# LDO_AUX.net
KiCad netlist of a schematic drawn in Altium Designer
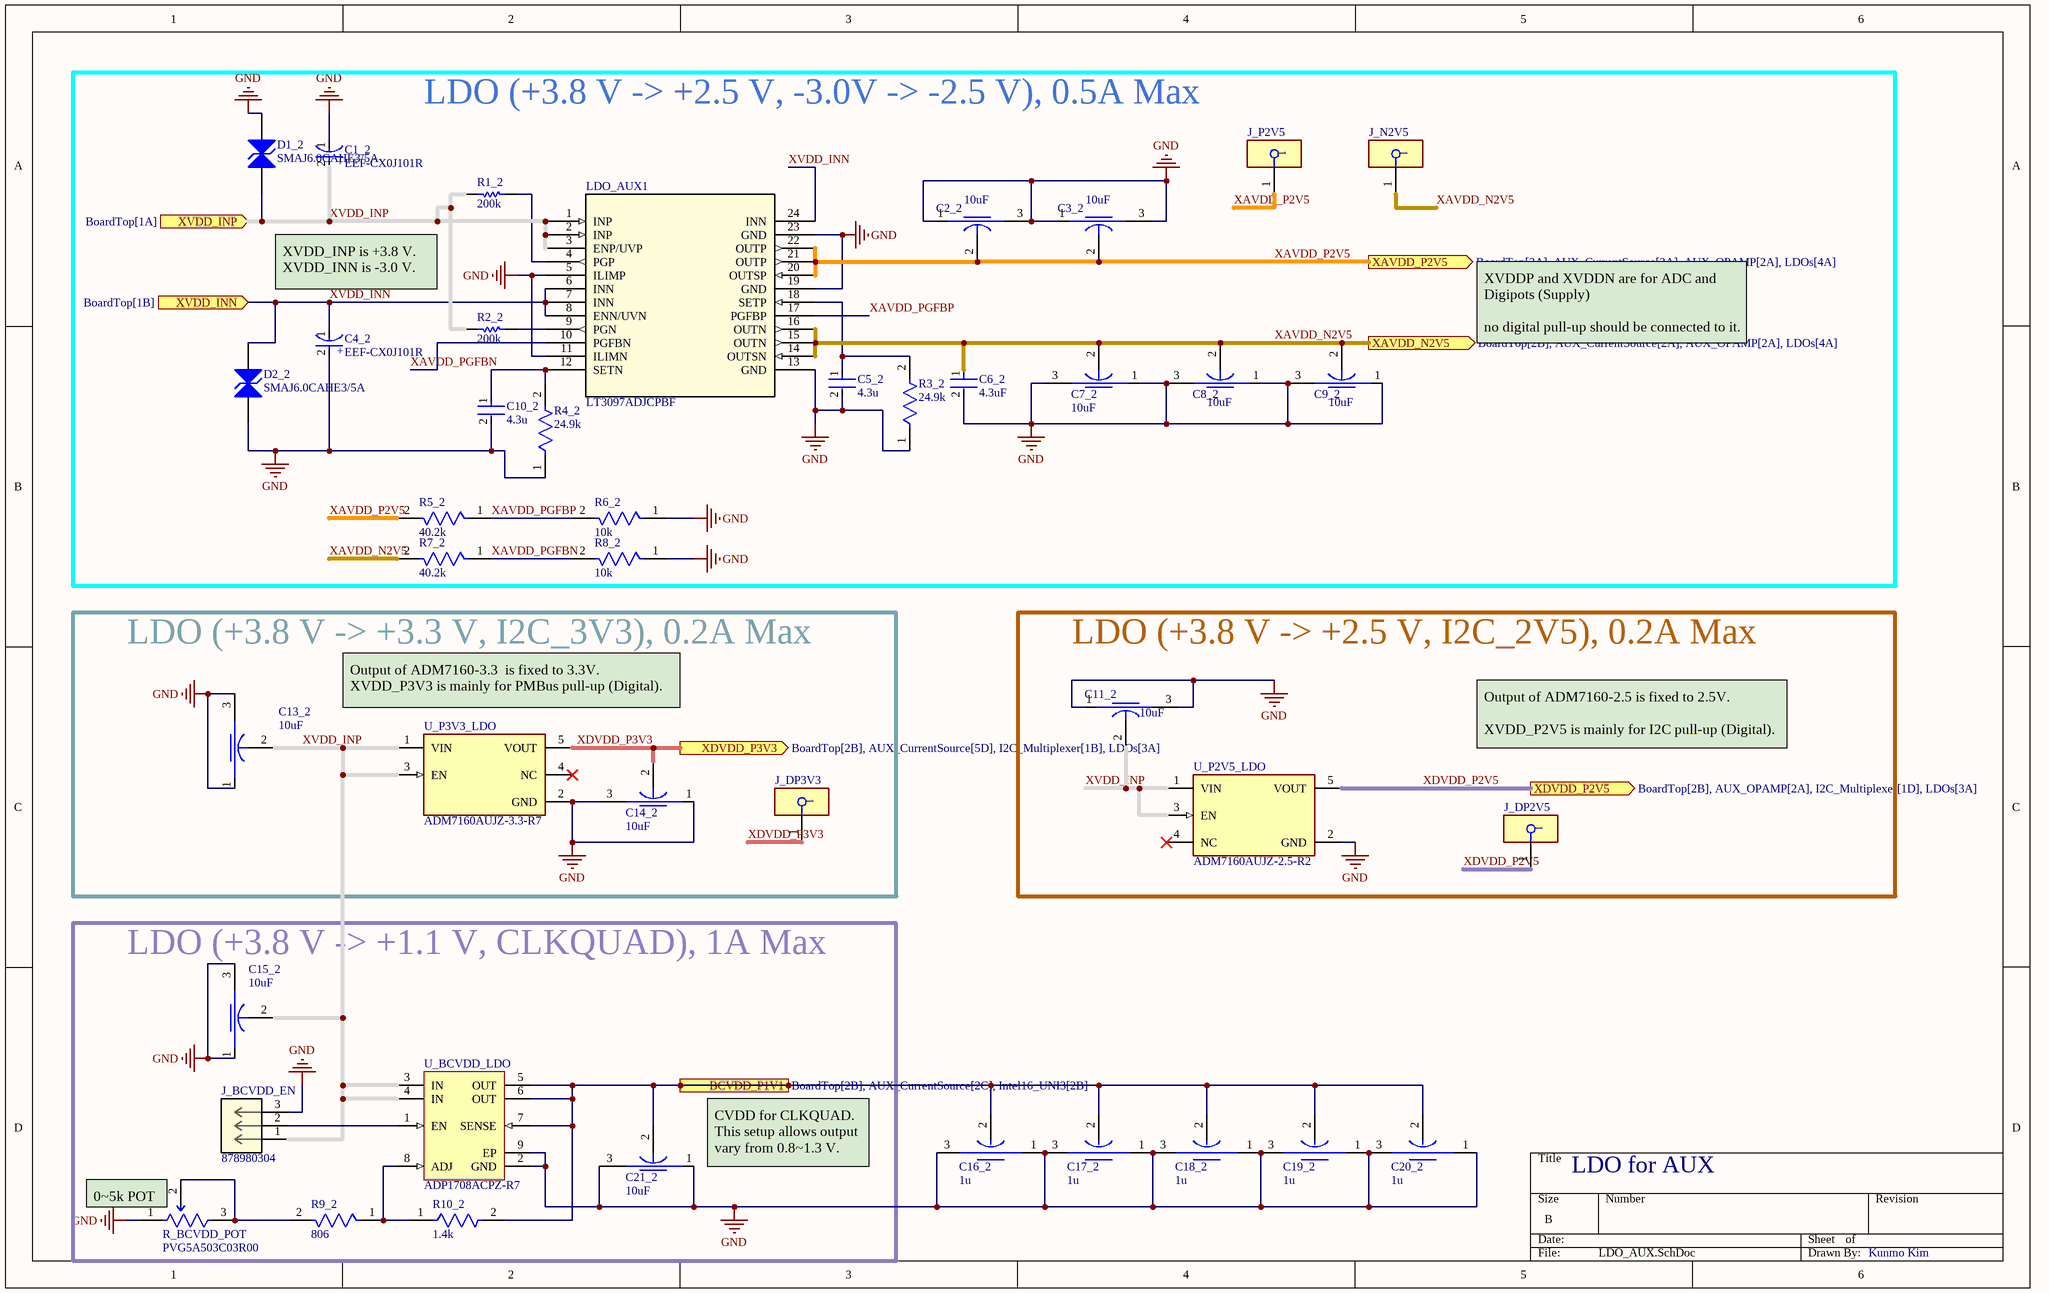
[diagram p0: LDO_AUX.SchDoc]

(export (version "E")
  (design (tool "Eeschema 10.0.6"))
  (components
    (comp (ref "C1_2")
      (value "EEF-CX0J101R")
      (footprint "FP-CX-MFG")
      (description "CAP ALUM POLY 100UF 20% 6.3V SMD")
      (fields (field (name "VOLTAGE") "6.3V") (field (name "TOLERANCE") "20%"))
      (libsource (lib "cap_SP_100uF") (part "CMP-05427-000056-1"))
    )
    (comp (ref "C2_2")
      (value "10uF")
      (footprint "FP-NFM15-0_2-MFG")
      (description "CAP FEEDTHRU")
      (libsource (lib "NFM15PC915") (part "CMP-06053-000058-1"))
    )
    (comp (ref "C3_2")
      (value "10uF")
      (footprint "FP-NFM15-0_2-MFG")
      (description "CAP FEEDTHRU")
      (libsource (lib "NFM15PC915") (part "CMP-06053-000058-1"))
    )
    (comp (ref "C4_2")
      (value "EEF-CX0J101R")
      (footprint "FP-CX-MFG")
      (description "CAP ALUM POLY 100UF 20% 6.3V SMD")
      (fields (field (name "VOLTAGE") "6.3V") (field (name "TOLERANCE") "20%"))
      (libsource (lib "cap_SP_100uF") (part "CMP-05427-000056-1"))
    )
    (comp (ref "C5_2")
      (value "4.3u")
      (footprint "FP-LLL1U4-0_05-IPC_C")
      (description "Cap Ceramic Monolithic 4.3uF 20% 4V X5R 15% 02404 (0610M)")
      (fields (field (name "TOLERANCE") "20%"))
      (libsource (lib "LLL_cap") (part "CMP-06035-061933-1"))
    )
    (comp (ref "C6_2")
      (value "4.3uF")
      (footprint "FP-LLL1U4-0_05-MFG")
      (description "Cap Ceramic Monolithic 4.3uF 20% 4V X5R 15% 02404 (0610M)")
      (fields (field (name "TOLERANCE") "20%"))
      (libsource (lib "LLL_cap") (part "CMP-06035-061933-1"))
    )
    (comp (ref "C7_2")
      (value "10uF")
      (footprint "FP-NFM15-0_2-MFG")
      (description "CAP FEEDTHRU")
      (libsource (lib "NFM15PC915") (part "CMP-06053-000058-1"))
    )
    (comp (ref "C8_2")
      (value "10uF")
      (footprint "FP-NFM15-0_2-MFG")
      (description "CAP FEEDTHRU")
      (libsource (lib "NFM15PC915") (part "CMP-06053-000058-1"))
    )
    (comp (ref "C9_2")
      (value "10uF")
      (footprint "FP-NFM15-0_2-MFG")
      (description "CAP FEEDTHRU")
      (libsource (lib "NFM15PC915") (part "CMP-06053-000058-1"))
    )
    (comp (ref "C10_2")
      (value "4.3u")
      (footprint "FP-LLL1U4-0_05-IPC_C")
      (description "Cap Ceramic Monolithic 4.3uF 20% 4V X5R 15% 02404 (0610M)")
      (fields (field (name "TOLERANCE") "20%"))
      (libsource (lib "LLL_cap") (part "CMP-06035-061933-1"))
    )
    (comp (ref "C11_2")
      (value "10uF")
      (footprint "FP-NFM15-0_2-MFG")
      (description "CAP FEEDTHRU")
      (libsource (lib "NFM15PC915") (part "CMP-06053-000058-1"))
    )
    (comp (ref "C13_2")
      (value "10uF")
      (footprint "FP-NFM15-0_2-MFG")
      (description "CAP FEEDTHRU")
      (libsource (lib "NFM15PC915") (part "CMP-06053-000058-1"))
    )
    (comp (ref "C14_2")
      (value "10uF")
      (footprint "FP-NFM15-0_2-MFG")
      (description "CAP FEEDTHRU")
      (libsource (lib "NFM15PC915") (part "CMP-06053-000058-1"))
    )
    (comp (ref "C15_2")
      (value "10uF")
      (footprint "FP-NFM15-0_2-MFG")
      (description "CAP FEEDTHRU")
      (libsource (lib "NFM15PC915") (part "CMP-06053-000058-1"))
    )
    (comp (ref "C16_2")
      (value "1u")
      (footprint "PCBComponent_1")
      (description "0402(1005M) 4V 1.0UF +/- 20% 3 T")
      (fields (field (name "TOLERANCE") "20%"))
      (libsource (lib "NFM15HC105D0G3D") (part "CMP-06053-000757-1"))
    )
    (comp (ref "C17_2")
      (value "1u")
      (footprint "PCBComponent_1")
      (description "0402(1005M) 4V 1.0UF +/- 20% 3 T")
      (fields (field (name "TOLERANCE") "20%"))
      (libsource (lib "NFM15HC105D0G3D") (part "CMP-06053-000757-1"))
    )
    (comp (ref "C18_2")
      (value "1u")
      (footprint "PCBComponent_1")
      (description "0402(1005M) 4V 1.0UF +/- 20% 3 T")
      (fields (field (name "TOLERANCE") "20%"))
      (libsource (lib "NFM15HC105D0G3D") (part "CMP-06053-000757-1"))
    )
    (comp (ref "C19_2")
      (value "1u")
      (footprint "PCBComponent_1")
      (description "0402(1005M) 4V 1.0UF +/- 20% 3 T")
      (fields (field (name "TOLERANCE") "20%"))
      (libsource (lib "NFM15HC105D0G3D") (part "CMP-06053-000757-1"))
    )
    (comp (ref "C20_2")
      (value "1u")
      (footprint "PCBComponent_1")
      (description "0402(1005M) 4V 1.0UF +/- 20% 3 T")
      (fields (field (name "TOLERANCE") "20%"))
      (libsource (lib "NFM15HC105D0G3D") (part "CMP-06053-000757-1"))
    )
    (comp (ref "C21_2")
      (value "10uF")
      (footprint "FP-NFM15-0_2-MFG")
      (description "CAP FEEDTHRU")
      (libsource (lib "NFM15PC915") (part "CMP-06053-000058-1"))
    )
    (comp (ref "D1_2")
      (value "SMAJ6.0CAHE3/5A")
      (footprint "VISH-DO-214AC-2_L")
      (fields (field (name "MANUFACTURER") "Vishay Semiconductor"))
      (libsource (lib "SMAJ6p0CAHE3") (part "CMP-0548-00108-2"))
    )
    (comp (ref "D2_2")
      (value "SMAJ6.0CAHE3/5A")
      (footprint "VISH-DO-214AC-2_L")
      (fields (field (name "MANUFACTURER") "Vishay Semiconductor"))
      (libsource (lib "SMAJ6p0CAHE3") (part "CMP-0548-00108-2"))
    )
    (comp (ref "J_BCVDD_EN")
      (value "878980304")
      (footprint "CONN03_87898_M-5p84_MOL")
      (description "No Description Available")
      (libsource (lib "878980304") (part "878980304"))
    )
    (comp (ref "J_DP2V5")
      (value "5019")
      (footprint "FP-5019-MFG")
      (libsource (lib "Altium Content Vault") (part "98815daf2f2c152b0c43f5ab9800df6"))
    )
    (comp (ref "J_DP3V3")
      (value "5019")
      (footprint "FP-5019-MFG")
      (libsource (lib "Altium Content Vault") (part "98815daf2f2c152b0c43f5ab9800df6"))
    )
    (comp (ref "J_N2V5")
      (value "5019")
      (footprint "FP-5019-MFG")
      (libsource (lib "Altium Content Vault") (part "98815daf2f2c152b0c43f5ab9800df6"))
    )
    (comp (ref "J_P2V5")
      (value "5019")
      (footprint "FP-5019-MFG")
      (libsource (lib "Altium Content Vault") (part "98815daf2f2c152b0c43f5ab9800df6"))
    )
    (comp (ref "LDO_AUX1")
      (value "LT3097ADJCPBF")
      (footprint "05-08-7071_ADI")
      (description "No Description Available")
      (libsource (lib "LT3097ADJCPBF") (part "LT3097ADJCPBF"))
    )
    (comp (ref "R1_2")
      (value "200k")
      (footprint "RESC1005X40X25NL05T05")
      (description "Chip Resistor, 200 KOhm, +/- 1%, 100 mW, -55 to 155 degC, 0402 (1005 Metric), RoHS, Tape and Reel")
      (fields (field (name "PARTNUMBER") "ERJ-2RKF2003X") (field (name "TOLERANCE") "1%"))
      (libsource (lib "Altium Content Vault") (part "RES-2"))
    )
    (comp (ref "R2_2")
      (value "200k")
      (footprint "RESC1005X40X25NL05T05")
      (description "Chip Resistor, 200 KOhm, +/- 1%, 100 mW, -55 to 155 degC, 0402 (1005 Metric), RoHS, Tape and Reel")
      (fields (field (name "PARTNUMBER") "ERJ-2RKF2003X") (field (name "TOLERANCE") "1%"))
      (libsource (lib "Altium Content Vault") (part "RES-2"))
    )
    (comp (ref "R3_2")
      (value "24.9k")
      (footprint "FP-ERJ2RK-MFG")
      (description "RES SMD 24.9K OHM 1% 1/10W 0402")
      (fields (field (name "TOLERANCE") "1%"))
      (libsource (lib "Altium Content Vault") (part "1029c3af85768c4190bb7ad29bc67b5"))
    )
    (comp (ref "R4_2")
      (value "24.9k")
      (footprint "FP-ERJ2RK-MFG")
      (description "RES SMD 24.9K OHM 1% 1/10W 0402")
      (fields (field (name "TOLERANCE") "1%"))
      (libsource (lib "Altium Content Vault") (part "1029c3af85768c4190bb7ad29bc67b5"))
    )
    (comp (ref "R5_2")
      (value "40.2k")
      (footprint "FP-ERJ2RK-MFG")
      (description "RES SMD 40.2K OHM 1% 1/10W 0402")
      (fields (field (name "TOLERANCE") "1%"))
      (libsource (lib "Altium Content Vault") (part "1029c3af85768c4190bb7ad29bc67b5"))
    )
    (comp (ref "R6_2")
      (value "10k")
      (footprint "FP-ERA2A-MFG")
      (description "RES SMD 10K OHM 0.1% 1/16W 0402")
      (fields (field (name "TOLERANCE") "0.1%") (field (name "MANUFACTURER PART NUMBER") "ERA-2AEB103X"))
      (libsource (lib "Altium Content Vault") (part "1029c3af85768c4190bb7ad29bc67b5"))
    )
    (comp (ref "R7_2")
      (value "40.2k")
      (footprint "FP-ERJ2RK-MFG")
      (description "RES SMD 40.2K OHM 1% 1/10W 0402")
      (fields (field (name "TOLERANCE") "1%"))
      (libsource (lib "Altium Content Vault") (part "1029c3af85768c4190bb7ad29bc67b5"))
    )
    (comp (ref "R8_2")
      (value "10k")
      (footprint "FP-ERA2A-MFG")
      (description "RES SMD 10K OHM 0.1% 1/16W 0402")
      (fields (field (name "TOLERANCE") "0.1%") (field (name "MANUFACTURER PART NUMBER") "ERA-2AEB103X"))
      (libsource (lib "Altium Content Vault") (part "1029c3af85768c4190bb7ad29bc67b5"))
    )
    (comp (ref "R9_2")
      (value "806")
      (footprint "FP-ERJ2RK-MFG")
      (description "RES SMD 80.6K OHM 1% 1/10W 0402")
      (fields (field (name "TOLERANCE") "1%"))
      (libsource (lib "Altium Content Vault") (part "1029c3af85768c4190bb7ad29bc67b5"))
    )
    (comp (ref "R10_2")
      (value "1.4k")
      (footprint "FP-RT0603-MFG")
      (description "RES SMD 1.4K OHM 0.1% 1/10W 0603")
      (fields (field (name "TOLERANCE") "0.001") (field (name "MANUFACTURER PART NUMBER") "RT0603BRD071K4L"))
      (libsource (lib "Altium Content Vault") (part "1029c3af85768c4190bb7ad29bc67b5"))
    )
    (comp (ref "R_BCVDD_POT")
      (value "PVG5A503C03R00")
      (footprint "FP-PVG5A-MFG")
      (description "PVG5A502C03R00 Resistor Trimmer, Cermet, 5 kOhm, ± 10%, 250 mW, 12 Turn, Multi Turn, Surface Mount")
      (fields (field (name "TOLERANCE") "10%"))
      (libsource (lib "PVG5A502C03R00") (part "CMP-00059-71526922-1"))
    )
    (comp (ref "U_BCVDD_LDO")
      (value "ADP1708ACPZ-R7")
      (footprint "ADI-CP-8-2_N")
      (fields (field (name "MANUFACTURER") "Analog Devices"))
      (libsource (lib "ADP1708ACPZ_R7") (part "CMP-0786-00092-1"))
    )
    (comp (ref "U_P2V5_LDO")
      (value "ADM7160AUJZ-2.5-R2")
      (footprint "FP-UJ-5-IPC_A")
      (description "IC REG LINEAR 2.5V 200MA TSOT5")
      (libsource (lib "ADM7160_P2V5") (part "CMP-09138-000128-1"))
    )
    (comp (ref "U_P3V3_LDO")
      (value "ADM7160AUJZ-3.3-R7")
      (footprint "FP-UJ-5-IPC_A")
      (description "IC REG LINEAR 3.3V 200MA TSOT5")
      (libsource (lib "ADM7160_P3V3") (part "CMP-09138-000051-1"))
    )
  )
  (nets
    (net (code "1") (name "/BCVDD_P1V1") (class "Default")
      (node (ref "C16_2") (pin "2") (pinfunction "GND_2") (pintype "passive"))
      (node (ref "C17_2") (pin "2") (pinfunction "GND_2") (pintype "passive"))
      (node (ref "C18_2") (pin "2") (pinfunction "GND_2") (pintype "passive"))
      (node (ref "C19_2") (pin "2") (pinfunction "GND_2") (pintype "passive"))
      (node (ref "C20_2") (pin "2") (pinfunction "GND_2") (pintype "passive"))
      (node (ref "C21_2") (pin "2") (pinfunction "GND_2") (pintype "passive"))
      (node (ref "R10_2") (pin "2") (pinfunction "2_2") (pintype "passive"))
      (node (ref "U_BCVDD_LDO") (pin "5") (pinfunction "OUT_5") (pintype "power_in"))
      (node (ref "U_BCVDD_LDO") (pin "6") (pinfunction "OUT_6") (pintype "power_in"))
      (node (ref "U_BCVDD_LDO") (pin "7") (pinfunction "SENSE_7") (pintype "input"))
    )
    (net (code "2") (name "/XAVDD_N2V5") (class "Default")
      (node (ref "C6_2") (pin "1") (pinfunction "1_1") (pintype "passive"))
      (node (ref "C7_2") (pin "2") (pinfunction "GND_2") (pintype "passive"))
      (node (ref "C8_2") (pin "2") (pinfunction "GND_2") (pintype "passive"))
      (node (ref "C9_2") (pin "2") (pinfunction "GND_2") (pintype "passive"))
      (node (ref "J_N2V5") (pin "1") (pinfunction "1_1") (pintype "passive"))
      (node (ref "LDO_AUX1") (pin "14") (pinfunction "OUTSN_14") (pintype "input"))
      (node (ref "LDO_AUX1") (pin "15") (pinfunction "OUTN_15") (pintype "output"))
      (node (ref "LDO_AUX1") (pin "16") (pinfunction "OUTN_16") (pintype "output"))
      (node (ref "R7_2") (pin "2") (pinfunction "2_2") (pintype "passive"))
    )
    (net (code "3") (name "/XAVDD_P2V5") (class "Default")
      (node (ref "C2_2") (pin "2") (pinfunction "GND_2") (pintype "passive"))
      (node (ref "C3_2") (pin "2") (pinfunction "GND_2") (pintype "passive"))
      (node (ref "J_P2V5") (pin "1") (pinfunction "1_1") (pintype "passive"))
      (node (ref "LDO_AUX1") (pin "20") (pinfunction "OUTSP_20") (pintype "input"))
      (node (ref "LDO_AUX1") (pin "21") (pinfunction "OUTP_21") (pintype "output"))
      (node (ref "LDO_AUX1") (pin "22") (pinfunction "OUTP_22") (pintype "output"))
      (node (ref "R5_2") (pin "2") (pinfunction "2_2") (pintype "passive"))
    )
    (net (code "4") (name "/XAVDD_PGFBN") (class "Default")
      (node (ref "LDO_AUX1") (pin "10") (pinfunction "PGFBN_10") (pintype "passive"))
      (node (ref "R7_2") (pin "1") (pinfunction "1_1") (pintype "passive"))
      (node (ref "R8_2") (pin "2") (pinfunction "2_2") (pintype "passive"))
    )
    (net (code "5") (name "/XAVDD_PGFBP") (class "Default")
      (node (ref "LDO_AUX1") (pin "17") (pinfunction "PGFBP_17") (pintype "passive"))
      (node (ref "R5_2") (pin "1") (pinfunction "1_1") (pintype "passive"))
      (node (ref "R6_2") (pin "2") (pinfunction "2_2") (pintype "passive"))
    )
    (net (code "6") (name "/XDVDD_P2V5") (class "Default")
      (node (ref "J_DP2V5") (pin "1") (pinfunction "1_1") (pintype "passive"))
      (node (ref "U_P2V5_LDO") (pin "5") (pinfunction "VOUT_5") (pintype "power_in"))
    )
    (net (code "7") (name "/XDVDD_P3V3") (class "Default")
      (node (ref "C14_2") (pin "2") (pinfunction "GND_2") (pintype "passive"))
      (node (ref "J_DP3V3") (pin "1") (pinfunction "1_1") (pintype "passive"))
      (node (ref "U_P3V3_LDO") (pin "5") (pinfunction "VOUT_5") (pintype "power_in"))
    )
    (net (code "8") (name "/XVDD_INN") (class "Default")
      (node (ref "C4_2") (pin "1") (pinfunction "C_1") (pintype "passive"))
      (node (ref "D2_2") (pin "2") (pinfunction "A2_2") (pintype "passive"))
      (node (ref "LDO_AUX1") (pin "24") (pinfunction "INN_24") (pintype "power_in"))
      (node (ref "LDO_AUX1") (pin "6") (pinfunction "INN_6") (pintype "power_in"))
      (node (ref "LDO_AUX1") (pin "7") (pinfunction "INN_7") (pintype "power_in"))
      (node (ref "LDO_AUX1") (pin "8") (pinfunction "ENN/UVN_8") (pintype "passive"))
    )
    (net (code "9") (name "/XVDD_INP") (class "Default")
      (node (ref "C11_2") (pin "2") (pinfunction "GND_2") (pintype "passive"))
      (node (ref "C13_2") (pin "2") (pinfunction "GND_2") (pintype "passive"))
      (node (ref "C15_2") (pin "2") (pinfunction "GND_2") (pintype "passive"))
      (node (ref "C1_2") (pin "2") (pinfunction "A_2") (pintype "passive"))
      (node (ref "D1_2") (pin "1") (pinfunction "A1_1") (pintype "passive"))
      (node (ref "J_BCVDD_EN") (pin "1") (pinfunction "1_1") (pintype "passive"))
      (node (ref "LDO_AUX1") (pin "1") (pinfunction "INP_1") (pintype "input"))
      (node (ref "LDO_AUX1") (pin "2") (pinfunction "INP_2") (pintype "input"))
      (node (ref "LDO_AUX1") (pin "3") (pinfunction "ENP/UVP_3") (pintype "passive"))
      (node (ref "R1_2") (pin "2") (pinfunction "2_2") (pintype "passive"))
      (node (ref "R2_2") (pin "2") (pinfunction "2_2") (pintype "passive"))
      (node (ref "U_BCVDD_LDO") (pin "3") (pinfunction "IN_3") (pintype "power_in"))
      (node (ref "U_BCVDD_LDO") (pin "4") (pinfunction "IN_4") (pintype "power_in"))
      (node (ref "U_P2V5_LDO") (pin "1") (pinfunction "VIN_1") (pintype "power_in"))
      (node (ref "U_P2V5_LDO") (pin "3") (pinfunction "EN_3") (pintype "input"))
      (node (ref "U_P3V3_LDO") (pin "1") (pinfunction "VIN_1") (pintype "power_in"))
      (node (ref "U_P3V3_LDO") (pin "3") (pinfunction "EN_3") (pintype "input"))
    )
    (net (code "10") (name "GND") (class "Default")
      (node (ref "C10_2") (pin "2") (pinfunction "2_2") (pintype "passive"))
      (node (ref "C11_2") (pin "1") (pinfunction "Input_1") (pintype "passive"))
      (node (ref "C11_2") (pin "3") (pinfunction "Output_3") (pintype "passive"))
      (node (ref "C13_2") (pin "1") (pinfunction "Input_1") (pintype "passive"))
      (node (ref "C13_2") (pin "3") (pinfunction "Output_3") (pintype "passive"))
      (node (ref "C14_2") (pin "1") (pinfunction "Input_1") (pintype "passive"))
      (node (ref "C14_2") (pin "3") (pinfunction "Output_3") (pintype "passive"))
      (node (ref "C15_2") (pin "1") (pinfunction "Input_1") (pintype "passive"))
      (node (ref "C15_2") (pin "3") (pinfunction "Output_3") (pintype "passive"))
      (node (ref "C16_2") (pin "1") (pinfunction "Input_1") (pintype "passive"))
      (node (ref "C16_2") (pin "3") (pinfunction "Output_3") (pintype "passive"))
      (node (ref "C17_2") (pin "1") (pinfunction "Input_1") (pintype "passive"))
      (node (ref "C17_2") (pin "3") (pinfunction "Output_3") (pintype "passive"))
      (node (ref "C18_2") (pin "1") (pinfunction "Input_1") (pintype "passive"))
      (node (ref "C18_2") (pin "3") (pinfunction "Output_3") (pintype "passive"))
      (node (ref "C19_2") (pin "1") (pinfunction "Input_1") (pintype "passive"))
      (node (ref "C19_2") (pin "3") (pinfunction "Output_3") (pintype "passive"))
      (node (ref "C1_2") (pin "1") (pinfunction "C_1") (pintype "passive"))
      (node (ref "C20_2") (pin "1") (pinfunction "Input_1") (pintype "passive"))
      (node (ref "C20_2") (pin "3") (pinfunction "Output_3") (pintype "passive"))
      (node (ref "C21_2") (pin "1") (pinfunction "Input_1") (pintype "passive"))
      (node (ref "C21_2") (pin "3") (pinfunction "Output_3") (pintype "passive"))
      (node (ref "C2_2") (pin "1") (pinfunction "Input_1") (pintype "passive"))
      (node (ref "C2_2") (pin "3") (pinfunction "Output_3") (pintype "passive"))
      (node (ref "C3_2") (pin "1") (pinfunction "Input_1") (pintype "passive"))
      (node (ref "C3_2") (pin "3") (pinfunction "Output_3") (pintype "passive"))
      (node (ref "C4_2") (pin "2") (pinfunction "A_2") (pintype "passive"))
      (node (ref "C5_2") (pin "2") (pinfunction "2_2") (pintype "passive"))
      (node (ref "C6_2") (pin "2") (pinfunction "2_2") (pintype "passive"))
      (node (ref "C7_2") (pin "1") (pinfunction "Input_1") (pintype "passive"))
      (node (ref "C7_2") (pin "3") (pinfunction "Output_3") (pintype "passive"))
      (node (ref "C8_2") (pin "1") (pinfunction "Input_1") (pintype "passive"))
      (node (ref "C8_2") (pin "3") (pinfunction "Output_3") (pintype "passive"))
      (node (ref "C9_2") (pin "1") (pinfunction "Input_1") (pintype "passive"))
      (node (ref "C9_2") (pin "3") (pinfunction "Output_3") (pintype "passive"))
      (node (ref "D1_2") (pin "2") (pinfunction "A2_2") (pintype "passive"))
      (node (ref "D2_2") (pin "1") (pinfunction "A1_1") (pintype "passive"))
      (node (ref "J_BCVDD_EN") (pin "3") (pinfunction "3_3") (pintype "passive"))
      (node (ref "LDO_AUX1") (pin "11") (pinfunction "ILIMN_11") (pintype "passive"))
      (node (ref "LDO_AUX1") (pin "13") (pinfunction "GND_13") (pintype "power_in"))
      (node (ref "LDO_AUX1") (pin "19") (pinfunction "GND_19") (pintype "power_in"))
      (node (ref "LDO_AUX1") (pin "23") (pinfunction "GND_23") (pintype "power_in"))
      (node (ref "LDO_AUX1") (pin "5") (pinfunction "ILIMP_5") (pintype "passive"))
      (node (ref "R3_2") (pin "1") (pinfunction "1_1") (pintype "passive"))
      (node (ref "R4_2") (pin "1") (pinfunction "1_1") (pintype "passive"))
      (node (ref "R6_2") (pin "1") (pinfunction "1_1") (pintype "passive"))
      (node (ref "R8_2") (pin "1") (pinfunction "1_1") (pintype "passive"))
      (node (ref "R_BCVDD_POT") (pin "1") (pinfunction "CCW_1") (pintype "passive"))
      (node (ref "U_BCVDD_LDO") (pin "2") (pinfunction "GND_2") (pintype "power_in"))
      (node (ref "U_BCVDD_LDO") (pin "9") (pinfunction "EP_9") (pintype "power_in"))
      (node (ref "U_P2V5_LDO") (pin "2") (pinfunction "GND_2") (pintype "power_in"))
      (node (ref "U_P3V3_LDO") (pin "2") (pinfunction "GND_2") (pintype "power_in"))
    )
    (net (code "11") (name "Net-(LDO_AUX1-PGN)") (class "Default")
      (node (ref "LDO_AUX1") (pin "9") (pinfunction "PGN_9") (pintype "output"))
      (node (ref "R2_2") (pin "1") (pinfunction "1_1") (pintype "passive"))
    )
    (net (code "12") (name "Net-(LDO_AUX1-PGP)") (class "Default")
      (node (ref "LDO_AUX1") (pin "4") (pinfunction "PGP_4") (pintype "output"))
      (node (ref "R1_2") (pin "1") (pinfunction "1_1") (pintype "passive"))
    )
    (net (code "13") (name "Net-(LDO_AUX1-SETN)") (class "Default")
      (node (ref "C10_2") (pin "1") (pinfunction "1_1") (pintype "passive"))
      (node (ref "LDO_AUX1") (pin "12") (pinfunction "SETN_12") (pintype "passive"))
      (node (ref "R4_2") (pin "2") (pinfunction "2_2") (pintype "passive"))
    )
    (net (code "14") (name "Net-(LDO_AUX1-SETP)") (class "Default")
      (node (ref "C5_2") (pin "1") (pinfunction "1_1") (pintype "passive"))
      (node (ref "LDO_AUX1") (pin "18") (pinfunction "SETP_18") (pintype "input"))
      (node (ref "R3_2") (pin "2") (pinfunction "2_2") (pintype "passive"))
    )
    (net (code "15") (name "Net-(R_BCVDD_POT-CW)") (class "Default")
      (node (ref "R9_2") (pin "2") (pinfunction "2_2") (pintype "passive"))
      (node (ref "R_BCVDD_POT") (pin "2") (pinfunction "WIPER_2") (pintype "passive"))
      (node (ref "R_BCVDD_POT") (pin "3") (pinfunction "CW_3") (pintype "passive"))
    )
    (net (code "16") (name "Net-(U_BCVDD_LDO-ADJ)") (class "Default")
      (node (ref "R10_2") (pin "1") (pinfunction "1_1") (pintype "passive"))
      (node (ref "R9_2") (pin "1") (pinfunction "1_1") (pintype "passive"))
      (node (ref "U_BCVDD_LDO") (pin "8") (pinfunction "ADJ_8") (pintype "input"))
    )
    (net (code "17") (name "Net-(U_BCVDD_LDO-EN)") (class "Default")
      (node (ref "J_BCVDD_EN") (pin "2") (pinfunction "2_2") (pintype "passive"))
      (node (ref "U_BCVDD_LDO") (pin "1") (pinfunction "EN_1") (pintype "input"))
    )
    (net (code "18") (name "unconnected-(U_P2V5_LDO-NC-Pad4)") (class "Default")
      (node (ref "U_P2V5_LDO") (pin "4") (pinfunction "NC_4") (pintype "passive+no_connect"))
    )
    (net (code "19") (name "unconnected-(U_P3V3_LDO-NC-Pad4)") (class "Default")
      (node (ref "U_P3V3_LDO") (pin "4") (pinfunction "NC_4") (pintype "passive+no_connect"))
    )
  )
)
